# Schematic.net
KiCad netlist of a schematic drawn in Altium Designer
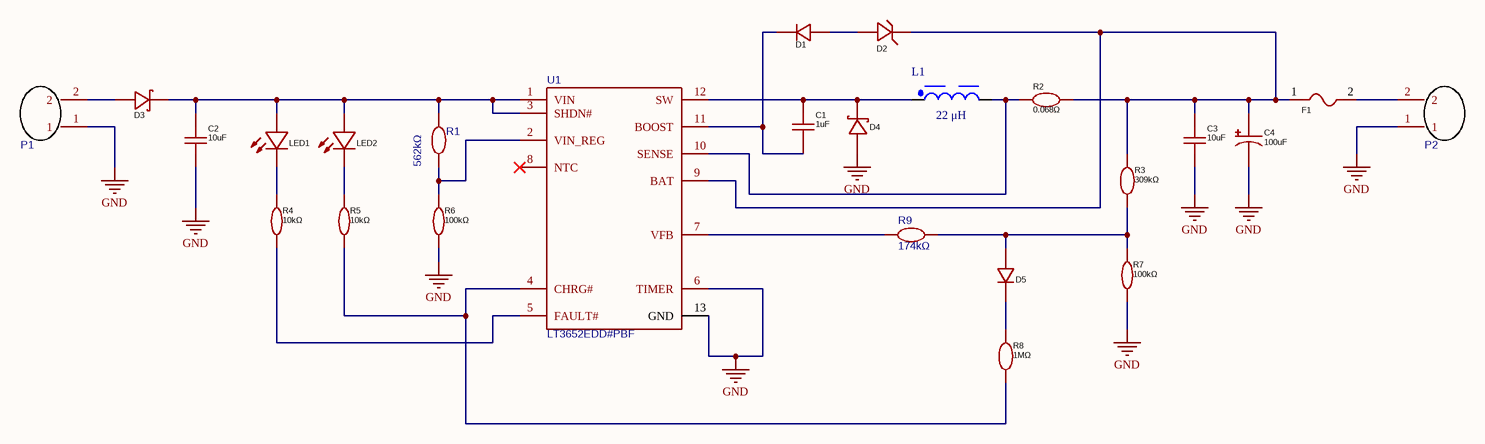
[diagram p0: Schematic.SchDoc]

(export (version "E")
  (design (tool "Eeschema 10.0.6"))
  (components
    (comp (ref "C1")
      (value "1uF")
      (footprint "C0805")
      (description "25V 1uF X5R ±10% 0805 Multilayer Ceramic Capacitors MLCC - SMD/SMT ROHS")
      (fields
        (field (name "MANUFACTURER") "muRata(村田)")
        (field (name "MANUFACTURER PART") "GRM216R61E105KA12D")
      )
      (libsource (lib "Capacitor") (part "GRM216R61E105KA12D"))
    )
    (comp (ref "C2")
      (value "10uF")
      (footprint "C1206")
      (description "35V 10uF X5R ±10% 1206 Multilayer Ceramic Capacitors MLCC - SMD/SMT ROHS")
      (fields
        (field (name "MANUFACTURER") "Murata Electronics")
        (field (name "MANUFACTURER PART") "GRT31CR6YA106KE01L")
      )
      (libsource (lib "Capacitor") (part "GRT31CR6YA106KE01L"))
    )
    (comp (ref "C3")
      (value "10uF")
      (footprint "C1206")
      (description "35V 10uF X5R ±10% 1206 Multilayer Ceramic Capacitors MLCC - SMD/SMT ROHS")
      (fields
        (field (name "MANUFACTURER") "Murata Electronics")
        (field (name "MANUFACTURER PART") "GRT31CR6YA106KE01L")
      )
      (libsource (lib "Capacitor") (part "GRT31CR6YA106KE01L"))
    )
    (comp (ref "C4")
      (value "100uF")
      (footprint "CAP-SMD_BD8.0-L8.3-W8.3-LS9.5-FD")
      (description "100uF 25V 130mA@120Hz ±20% SMD,D8xL10.2mm Aluminum Electrolytic Capacitors - SMD ROHS")
      (fields (field (name "MANUFACTURER") "PANASONIC(松下)") (field (name "MANUFACTURER PART") "EEEHC1E101P"))
      (libsource (lib "Capacitor") (part "EEEHC1E101P"))
    )
    (comp (ref "D1")
      (value "1N4148WS-7-F")
      (footprint "SOD-323_L1.8-W1.3-LS2.5-RD")
      (description "75V Independent Type 1.25V@150mA 4ns 150mA SOD-323 Switching Diodes ROHS")
      (fields (field (name "MANUFACTURER") "DIODES(美台)"))
      (libsource (lib "1N4148WS-7-F") (part "1N4148WS-7-F"))
    )
    (comp (ref "D2")
      (value "MMSZ5234BT1G")
      (footprint "SOD-123_L2.8-W1.8-LS3.7-RD")
      (description "Independent Type 5.89V~6.51V 500mW 6.2V SOD-123 Zener Diodes ROHS")
      (fields (field (name "MANUFACTURER") "onsemi(安森美)"))
      (libsource (lib "MMSZ5234BT1G") (part "MMSZ5234BT1G"))
    )
    (comp (ref "D3")
      (value "V8PAL45-M3/I")
      (footprint "DO-221BC_L4.3-W2.7-LS5.3-RD")
      (description "45V 4A 570mV@8A DO-221BC(SMPA) Schottky Diodes ROHS")
      (fields (field (name "MANUFACTURER") "VISHAY(威世)"))
      (libsource (lib "V8PAL45-M3") (part "V8PAL45-M3/I"))
    )
    (comp (ref "D4")
      (value "V8PAL45-M3/I")
      (footprint "DO-221BC_L4.3-W2.7-LS5.3-RD")
      (description "45V 4A 570mV@8A DO-221BC(SMPA) Schottky Diodes ROHS")
      (fields (field (name "MANUFACTURER") "VISHAY(威世)"))
      (libsource (lib "V8PAL45-M3") (part "V8PAL45-M3/I"))
    )
    (comp (ref "D5")
      (value "1N4148WS-7-F")
      (footprint "SOD-323_L1.8-W1.3-LS2.5-RD")
      (description "75V Independent Type 1.25V@150mA 4ns 150mA SOD-323 Switching Diodes ROHS")
      (fields (field (name "MANUFACTURER") "DIODES(美台)"))
      (libsource (lib "1N4148WS-7-F") (part "1N4148WS-7-F"))
    )
    (comp (ref "F1")
      (value "0437003.WR")
      (footprint "F1206")
      (description "50A SMD Fuse 3A 32V 1206 Disposable fuses ROHS")
      (fields (field (name "MANUFACTURER") "Littelfuse(美国力特)"))
      (libsource (lib "Fuse") (part "Fuse"))
    )
    (comp (ref "L1")
      (value "22 μH")
      (footprint "WE-PD_7345R")
      (description "WE-PD SMT Power Inductor, size 7345R, 22 μH, 1.41 A, 110 mΩ")
      (fields
        (field (name "MANUFACTURER PART NUMBER") "7447779122")
        (field (name "MANUFACTURER") "Wurth Elektronik")
      )
      (libsource (lib "WE-PD") (part "7447779122"))
    )
    (comp (ref "LED1")
      (value "LTST-C170KRKT")
      (footprint "LED0805-R-RD")
      (fields (field (name "MANUFACTURER") "LITEON(光宝)"))
      (libsource (lib "LED") (part "LTST-C170KRKT"))
    )
    (comp (ref "LED2")
      (value "LTST-C170KRKT")
      (footprint "LED0805-R-RD")
      (fields (field (name "MANUFACTURER") "LITEON(光宝)"))
      (libsource (lib "LED") (part "LTST-C170KRKT"))
    )
    (comp (ref "P1")
      (value "WJ128V-5.0-2P")
      (footprint "CONN-TH_2P-P5.00_WJ128V-5.0-2P")
      (fields (field (name "MANUFACTURER") "KANGNEX(康奈克斯电气)"))
      (libsource (lib "2P terminal") (part "WJ128V-5.0-2P"))
    )
    (comp (ref "P2")
      (value "WJ128V-5.0-2P")
      (footprint "CONN-TH_2P-P5.00_WJ128V-5.0-2P")
      (fields (field (name "MANUFACTURER") "KANGNEX(康奈克斯电气)"))
      (libsource (lib "2P terminal") (part "WJ128V-5.0-2P"))
    )
    (comp (ref "R1")
      (value "562kΩ")
      (footprint "R0805")
      (description "0.125W Thick Film Resistors ±100ppm/℃ ±1% 562kΩ 0805 Chip Resistor - Surface Mount ROHS")
      (fields
        (field (name "MANUFACTURER") "PANASONIC(松下)")
        (field (name "MANUFACTURER PART") "ERJ6ENF5623V")
        (field (name "CONTRIBUTOR") "LCSC")
      )
      (libsource (lib "Resistor") (part "ERJ6ENF5623V"))
    )
    (comp (ref "R2")
      (value "0.068Ω")
      (footprint "R0805")
      (description "0.125W Thick Film Resistors 300V ±600ppm/℃ ±5% 0.068Ω 0805 Chip Resistor - Surface Mount ROHS")
      (fields (field (name "MANUFACTURER") "FOJAN") (field (name "MANUFACTURER PART") "FRL0805JR068TS"))
      (libsource (lib "Resistor") (part "FRL0805JR068TS"))
    )
    (comp (ref "R3")
      (value "309kΩ")
      (footprint "R0805")
      (description "309kΩ 0805 Chip Resistor 0.125W Thick Film Resistors ±100ppm/℃ ±1%  - Surface Mount ROHS")
      (fields (field (name "MANUFACTURER") "PANASONIC(松下)") (field (name "MANUFACTURER PART") "ERJ6ENF3093V"))
      (libsource (lib "Resistor") (part "ERJ6ENF3093V"))
    )
    (comp (ref "R4")
      (value "10kΩ")
      (footprint "R0805")
      (description "10kΩ 0805 Chip Resistor  0.2W Thick Film Resistors 200V ±50ppm/℃ ±0.1% - Surface Mount ROHS")
      (fields (field (name "MANUFACTURER") "PANASONIC(松下)") (field (name "MANUFACTURER PART") "ERJPB6B1002V"))
      (libsource (lib "Resistor") (part "ERJPB6B1002V"))
    )
    (comp (ref "R5")
      (value "10kΩ")
      (footprint "R0805")
      (description "10kΩ 0805 Chip Resistor  0.2W Thick Film Resistors 200V ±50ppm/℃ ±0.1% - Surface Mount ROHS")
      (fields (field (name "MANUFACTURER") "PANASONIC(松下)") (field (name "MANUFACTURER PART") "ERJPB6B1002V"))
      (libsource (lib "Resistor") (part "ERJPB6B1002V"))
    )
    (comp (ref "R6")
      (value "100kΩ")
      (footprint "R0805")
      (description "100kΩ 0805 Chip Resistor 0.125W Thick Film Resistors ±100ppm/℃ ±1%  - Surface Mount ROHS")
      (fields (field (name "MANUFACTURER") "PANASONIC(松下)") (field (name "MANUFACTURER PART") "ERJ6ENF1003V"))
      (libsource (lib "Resistor") (part "ERJ6ENF1003V"))
    )
    (comp (ref "R7")
      (value "100kΩ")
      (footprint "R0805")
      (description "100kΩ 0805 Chip Resistor 0.125W Thick Film Resistors ±100ppm/℃ ±1%  - Surface Mount ROHS")
      (fields (field (name "MANUFACTURER") "PANASONIC(松下)") (field (name "MANUFACTURER PART") "ERJ6ENF1003V"))
      (libsource (lib "Resistor") (part "ERJ6ENF1003V"))
    )
    (comp (ref "R8")
      (value "1MΩ")
      (footprint "R0805")
      (description "1MΩ 0805 Chip Resistor  0.5W Thick Film Resistors ±5% ±200ppm/℃ - Surface Mount ROHS")
      (fields (field (name "MANUFACTURER") "PANASONIC(松下)") (field (name "MANUFACTURER PART") "ERJP06J105V"))
      (libsource (lib "Resistor") (part "ERJP06J105V"))
    )
    (comp (ref "R9")
      (value "174kΩ")
      (footprint "R0805")
      (description "174kΩ 0805 Chip Resistor  0.125W Thick Film Resistors ±100ppm/℃ ±1% - Surface Mount ROHS")
      (fields
        (field (name "MANUFACTURER") "PANASONIC(松下)")
        (field (name "MANUFACTURER PART") "ERJ6ENF1743V")
        (field (name "CONTRIBUTOR") "LCSC")
      )
      (libsource (lib "Resistor") (part "ERJ6ENF1743V"))
    )
    (comp (ref "U1")
      (value "LT3652EDD#PBF")
      (footprint "DFN-12_L3.0-W3.0-P0.50-LS3.0-BL-EP")
      (description "4.95V~32V Multi-Chemical 1~4 2A DFN-12(3x3) Battery Management ROHS")
      (fields (field (name "MANUFACTURER") "ADI(亚德诺)"))
      (libsource (lib "LT3652EDD#PBF") (part "LT3652EDD#PBF"))
    )
  )
  (nets
    (net (code "1") (name "GND") (class "Default")
      (node (ref "C2") (pin "2") (pinfunction "2_2") (pintype "passive"))
      (node (ref "C3") (pin "1") (pinfunction "1_1") (pintype "passive"))
      (node (ref "C4") (pin "2") (pinfunction "2_2") (pintype "passive"))
      (node (ref "D4") (pin "2") (pinfunction "K_2") (pintype "passive"))
      (node (ref "P1") (pin "1") (pinfunction "1_1") (pintype "passive"))
      (node (ref "P2") (pin "1") (pinfunction "1_1") (pintype "passive"))
      (node (ref "R6") (pin "1") (pinfunction "1_1") (pintype "passive"))
      (node (ref "R7") (pin "1") (pinfunction "1_1") (pintype "passive"))
      (node (ref "U1") (pin "13") (pinfunction "GND_13") (pintype "passive"))
      (node (ref "U1") (pin "6") (pinfunction "TIMER_6") (pintype "passive"))
    )
    (net (code "2") (name "Net-(D1-A)") (class "Default")
      (node (ref "D1") (pin "2") (pinfunction "A_2") (pintype "passive"))
      (node (ref "D2") (pin "2") (pinfunction "A_2") (pintype "passive"))
    )
    (net (code "3") (name "Net-(D1-C)") (class "Default")
      (node (ref "C1") (pin "1") (pinfunction "1_1") (pintype "passive"))
      (node (ref "D1") (pin "1") (pinfunction "C_1") (pintype "passive"))
      (node (ref "U1") (pin "11") (pinfunction "BOOST_11") (pintype "passive"))
    )
    (net (code "4") (name "Net-(D2-C)") (class "Default")
      (node (ref "C3") (pin "2") (pinfunction "2_2") (pintype "passive"))
      (node (ref "C4") (pin "1") (pinfunction "1_1") (pintype "passive"))
      (node (ref "D2") (pin "1") (pinfunction "C_1") (pintype "passive"))
      (node (ref "F1") (pin "1") (pinfunction "1_1") (pintype "passive"))
      (node (ref "R2") (pin "2") (pinfunction "2_2") (pintype "passive"))
      (node (ref "R3") (pin "2") (pinfunction "2_2") (pintype "passive"))
      (node (ref "U1") (pin "9") (pinfunction "BAT_9") (pintype "passive"))
    )
    (net (code "5") (name "Net-(D3-A)") (class "Default")
      (node (ref "C2") (pin "1") (pinfunction "1_1") (pintype "passive"))
      (node (ref "D3") (pin "1") (pinfunction "A_1") (pintype "passive"))
      (node (ref "LED1") (pin "1") (pinfunction "+_1") (pintype "passive"))
      (node (ref "LED2") (pin "1") (pinfunction "+_1") (pintype "passive"))
      (node (ref "R1") (pin "2") (pinfunction "2_2") (pintype "passive"))
      (node (ref "U1") (pin "1") (pinfunction "VIN_1") (pintype "passive"))
      (node (ref "U1") (pin "3") (pinfunction "SHDN#_3") (pintype "passive"))
    )
    (net (code "6") (name "Net-(D3-K)") (class "Default")
      (node (ref "D3") (pin "2") (pinfunction "K_2") (pintype "passive"))
      (node (ref "P1") (pin "2") (pinfunction "2_2") (pintype "passive"))
    )
    (net (code "7") (name "Net-(D4-A)") (class "Default")
      (node (ref "C1") (pin "2") (pinfunction "2_2") (pintype "passive"))
      (node (ref "D4") (pin "1") (pinfunction "A_1") (pintype "passive"))
      (node (ref "L1") (pin "1") (pinfunction "1_1") (pintype "passive"))
      (node (ref "U1") (pin "12") (pinfunction "SW_12") (pintype "passive"))
    )
    (net (code "8") (name "Net-(D5-A)") (class "Default")
      (node (ref "D5") (pin "2") (pinfunction "A_2") (pintype "passive"))
      (node (ref "R3") (pin "1") (pinfunction "1_1") (pintype "passive"))
      (node (ref "R7") (pin "2") (pinfunction "2_2") (pintype "passive"))
      (node (ref "R9") (pin "2") (pinfunction "2_2") (pintype "passive"))
    )
    (net (code "9") (name "Net-(D5-C)") (class "Default")
      (node (ref "D5") (pin "1") (pinfunction "C_1") (pintype "passive"))
      (node (ref "R8") (pin "2") (pinfunction "2_2") (pintype "passive"))
    )
    (net (code "10") (name "Net-(F1-Pad2)") (class "Default")
      (node (ref "F1") (pin "2") (pinfunction "2_2") (pintype "passive"))
      (node (ref "P2") (pin "2") (pinfunction "2_2") (pintype "passive"))
    )
    (net (code "11") (name "Net-(LED1--)") (class "Default")
      (node (ref "LED1") (pin "2") (pinfunction "-_2") (pintype "passive"))
      (node (ref "R4") (pin "2") (pinfunction "2_2") (pintype "passive"))
    )
    (net (code "12") (name "Net-(LED2--)") (class "Default")
      (node (ref "LED2") (pin "2") (pinfunction "-_2") (pintype "passive"))
      (node (ref "R5") (pin "2") (pinfunction "2_2") (pintype "passive"))
    )
    (net (code "13") (name "Net-(U1-CHRG#)") (class "Default")
      (node (ref "R5") (pin "1") (pinfunction "1_1") (pintype "passive"))
      (node (ref "R8") (pin "1") (pinfunction "1_1") (pintype "passive"))
      (node (ref "U1") (pin "4") (pinfunction "CHRG#_4") (pintype "passive"))
    )
    (net (code "14") (name "Net-(U1-FAULT#)") (class "Default")
      (node (ref "R4") (pin "1") (pinfunction "1_1") (pintype "passive"))
      (node (ref "U1") (pin "5") (pinfunction "FAULT#_5") (pintype "passive"))
    )
    (net (code "15") (name "Net-(U1-SENSE)") (class "Default")
      (node (ref "L1") (pin "2") (pinfunction "2_2") (pintype "passive"))
      (node (ref "R2") (pin "1") (pinfunction "1_1") (pintype "passive"))
      (node (ref "U1") (pin "10") (pinfunction "SENSE_10") (pintype "passive"))
    )
    (net (code "16") (name "Net-(U1-VFB)") (class "Default")
      (node (ref "R9") (pin "1") (pinfunction "1_1") (pintype "passive"))
      (node (ref "U1") (pin "7") (pinfunction "VFB_7") (pintype "passive"))
    )
    (net (code "17") (name "Net-(U1-VIN_REG)") (class "Default")
      (node (ref "R1") (pin "1") (pinfunction "1_1") (pintype "passive"))
      (node (ref "R6") (pin "2") (pinfunction "2_2") (pintype "passive"))
      (node (ref "U1") (pin "2") (pinfunction "VIN_REG_2") (pintype "passive"))
    )
    (net (code "18") (name "unconnected-(U1-NTC-Pad8)") (class "Default")
      (node (ref "U1") (pin "8") (pinfunction "NTC_8") (pintype "passive+no_connect"))
    )
  )
)
